# ChargerLED.net
KiCad netlist of a schematic drawn in EAGLE
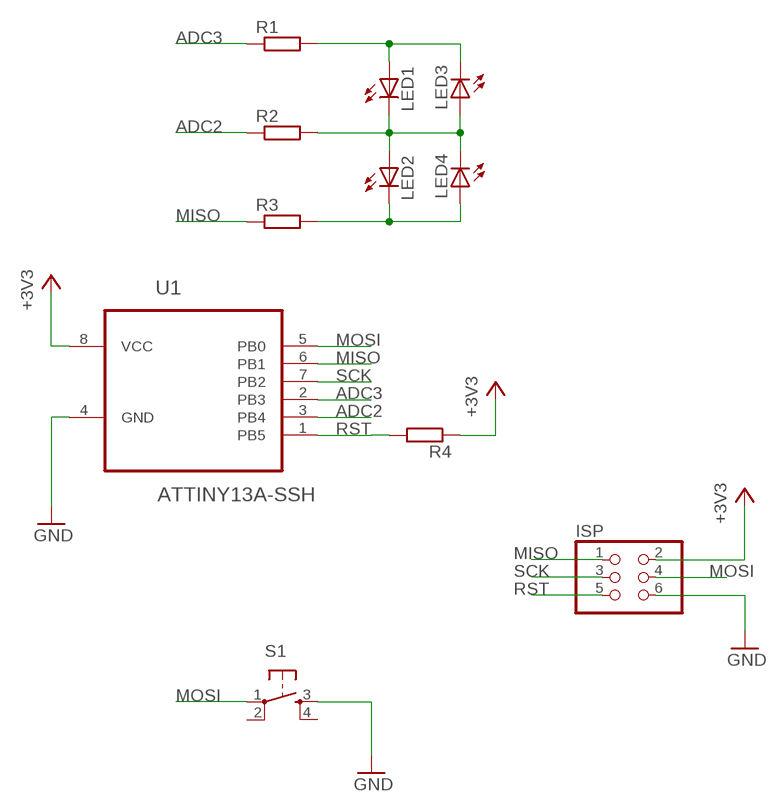
[diagram p0: schematic, sheet 1]

(export (version "E")
  (design (tool "Eeschema 10.0.6"))
  (components
    (comp (ref "ISP")
      (value "PINHD-2X3")
      (footprint "eagle-import:2X03")
      (libsource (lib "eagle-import") (part "PINHD-2X3"))
    )
    (comp (ref "LED1")
      (value "LEDCHIP-LED0603")
      (footprint "eagle-import:CHIP-LED0603")
      (libsource (lib "eagle-import") (part "LEDCHIP-LED0603"))
    )
    (comp (ref "LED2")
      (value "LEDCHIP-LED0603")
      (footprint "eagle-import:CHIP-LED0603")
      (libsource (lib "eagle-import") (part "LEDCHIP-LED0603"))
    )
    (comp (ref "LED3")
      (value "LEDCHIP-LED0603")
      (footprint "eagle-import:CHIP-LED0603")
      (libsource (lib "eagle-import") (part "LEDCHIP-LED0603"))
    )
    (comp (ref "LED4")
      (value "LEDCHIP-LED0603")
      (footprint "eagle-import:CHIP-LED0603")
      (libsource (lib "eagle-import") (part "LEDCHIP-LED0603"))
    )
    (comp (ref "R1")
      (value "R-EU_R0603")
      (footprint "eagle-import:R0603")
      (libsource (lib "eagle-import") (part "R-EU_R0603"))
    )
    (comp (ref "R2")
      (value "R-EU_R0603")
      (footprint "eagle-import:R0603")
      (libsource (lib "eagle-import") (part "R-EU_R0603"))
    )
    (comp (ref "R3")
      (value "R-EU_R0603")
      (footprint "eagle-import:R0603")
      (libsource (lib "eagle-import") (part "R-EU_R0603"))
    )
    (comp (ref "R4")
      (value "R-EU_R0603")
      (footprint "eagle-import:R0603")
      (libsource (lib "eagle-import") (part "R-EU_R0603"))
    )
    (comp (ref "S1")
      (value "TAC_SWITCHSMD")
      (footprint "eagle-import:TACTILE_SWITCH_SMD")
      (libsource (lib "eagle-import") (part "TAC_SWITCHSMD"))
    )
    (comp (ref "U1")
      (value "ATTINY13A-SSH")
      (footprint "eagle-import:SOIC127P600X175-8N")
      (libsource (lib "eagle-import") (part "ATTINY13A-SSH"))
    )
  )
  (nets
    (net (code "1") (name "+3V3") (class "Default")
      (node (ref "ISP") (pin "2") (pinfunction "2_2") (pintype "passive"))
      (node (ref "R4") (pin "1") (pinfunction "1_1") (pintype "passive"))
      (node (ref "U1") (pin "8") (pinfunction "VCC_8") (pintype "power_in"))
    )
    (net (code "2") (name "/ADC2") (class "Default")
      (node (ref "R2") (pin "1") (pinfunction "1_1") (pintype "passive"))
      (node (ref "U1") (pin "3") (pinfunction "PB4_3") (pintype "bidirectional"))
    )
    (net (code "3") (name "/ADC3") (class "Default")
      (node (ref "R1") (pin "1") (pinfunction "1_1") (pintype "passive"))
      (node (ref "U1") (pin "2") (pinfunction "PB3_2") (pintype "bidirectional"))
    )
    (net (code "4") (name "/MISO") (class "Default")
      (node (ref "ISP") (pin "1") (pinfunction "1_1") (pintype "passive"))
      (node (ref "R3") (pin "1") (pinfunction "1_1") (pintype "passive"))
      (node (ref "U1") (pin "6") (pinfunction "PB1_6") (pintype "bidirectional"))
    )
    (net (code "5") (name "/MOSI") (class "Default")
      (node (ref "ISP") (pin "4") (pinfunction "4_4") (pintype "passive"))
      (node (ref "S1") (pin "1") (pinfunction "1_1") (pintype "passive"))
      (node (ref "U1") (pin "5") (pinfunction "PB0_5") (pintype "bidirectional"))
    )
    (net (code "6") (name "/RST") (class "Default")
      (node (ref "ISP") (pin "5") (pinfunction "5_5") (pintype "passive"))
      (node (ref "R4") (pin "2") (pinfunction "2_2") (pintype "passive"))
      (node (ref "U1") (pin "1") (pinfunction "PB5_1") (pintype "bidirectional"))
    )
    (net (code "7") (name "/SCK") (class "Default")
      (node (ref "ISP") (pin "3") (pinfunction "3_3") (pintype "passive"))
      (node (ref "U1") (pin "7") (pinfunction "PB2_7") (pintype "bidirectional"))
    )
    (net (code "8") (name "GND") (class "Default")
      (node (ref "ISP") (pin "6") (pinfunction "6_6") (pintype "passive"))
      (node (ref "S1") (pin "3") (pinfunction "3_3") (pintype "passive"))
      (node (ref "U1") (pin "4") (pinfunction "GND_4") (pintype "passive"))
    )
    (net (code "9") (name "Net-(LED1-PadA)") (class "Default")
      (node (ref "LED1") (pin "A") (pinfunction "A_A") (pintype "passive"))
      (node (ref "LED3") (pin "C") (pinfunction "C_C") (pintype "passive"))
      (node (ref "R1") (pin "2") (pinfunction "2_2") (pintype "passive"))
    )
    (net (code "10") (name "Net-(LED1-PadC)") (class "Default")
      (node (ref "LED1") (pin "C") (pinfunction "C_C") (pintype "passive"))
      (node (ref "LED2") (pin "A") (pinfunction "A_A") (pintype "passive"))
      (node (ref "LED3") (pin "A") (pinfunction "A_A") (pintype "passive"))
      (node (ref "LED4") (pin "C") (pinfunction "C_C") (pintype "passive"))
      (node (ref "R2") (pin "2") (pinfunction "2_2") (pintype "passive"))
    )
    (net (code "11") (name "Net-(LED2-PadC)") (class "Default")
      (node (ref "LED2") (pin "C") (pinfunction "C_C") (pintype "passive"))
      (node (ref "LED4") (pin "A") (pinfunction "A_A") (pintype "passive"))
      (node (ref "R3") (pin "2") (pinfunction "2_2") (pintype "passive"))
    )
    (net (code "12") (name "unconnected-(S1-Pad2)") (class "Default")
      (node (ref "S1") (pin "2") (pinfunction "2_2") (pintype "passive"))
    )
    (net (code "13") (name "unconnected-(S1-Pad4)") (class "Default")
      (node (ref "S1") (pin "4") (pinfunction "4_4") (pintype "passive"))
    )
  )
)
